# MCU.net
KiCad netlist of a schematic drawn in Altium Designer
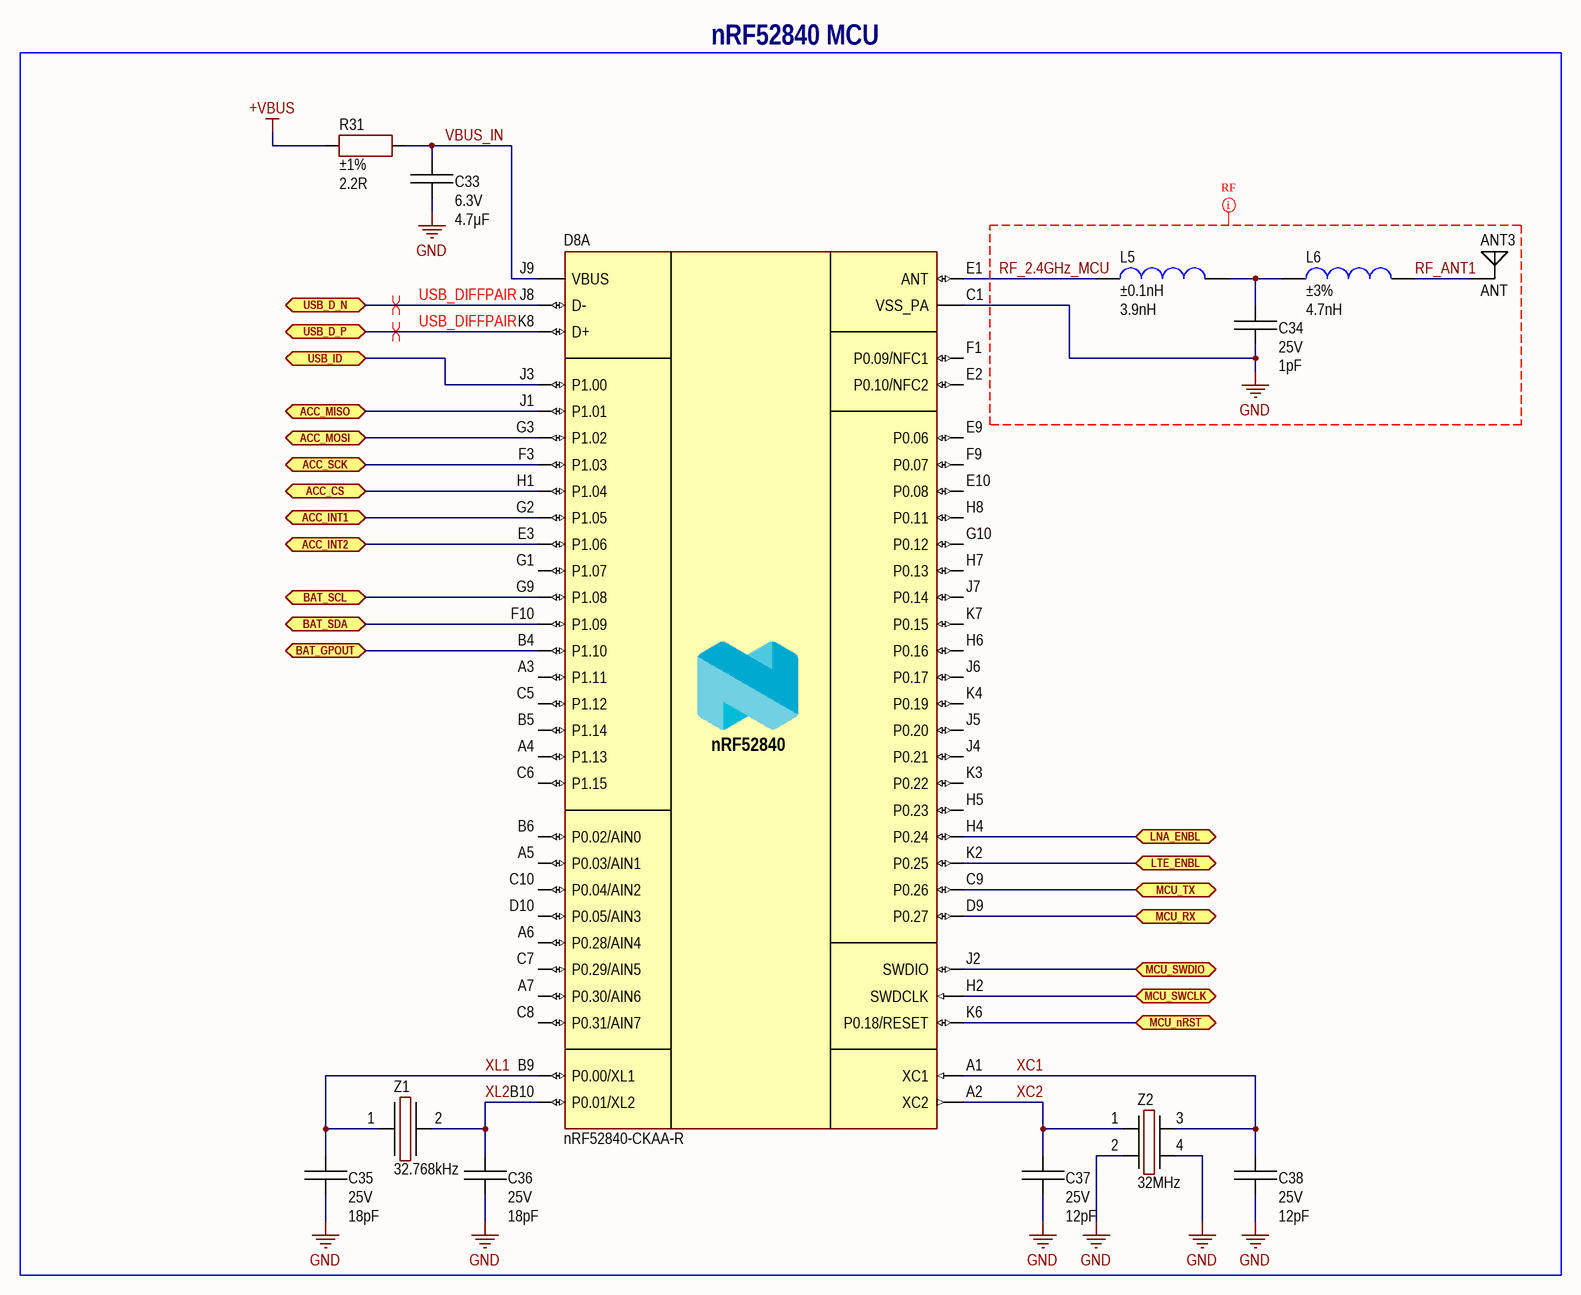
[diagram p0: MCU.SchDoc]

(export (version "E")
  (design (tool "Eeschema 10.0.6"))
  (components
    (comp (ref "ANT3")
      (value "~")
      (footprint "ANT: ANT2012LL00R2400A")
      (description "2.45GHz Bluetooth, ISM, Wi-Fi, Zigbee Chip RF Antenna 2.4GHz ~ 2.5GHz 3.77dBi Solder Surface Mount")
      (fields
        (field (name "MANUFACTURER") "Yageo")
        (field (name "VALUEMANUFACTURERPARTNUMBER") "Ceramic antenna, 2x1.25mm")
        (field (name "COMMENTTEXT") "ANT")
      )
      (libsource (lib "MyLib") (part "ANT2012LL00R2400A"))
    )
    (comp (ref "C33")
      (value "4.7μF")
      (footprint "CAP: 0603_NO_SILK")
      (description "4.7 µF ±20% 6.3V Ceramic Capacitor X7R 0603 (1608 Metric)")
      (fields
        (field (name "MANUFACTURER") "Yageo")
        (field (name "PARTNUMBER") "CC0603MRX7R5BB475")
        (field (name "VOLTAGE") "6.3V")
      )
      (libsource (lib "capacitor") (part "Ceramic_0603"))
    )
    (comp (ref "C34")
      (value "1pF")
      (footprint "CAP: 0201")
      (description "1 pF ±0.05pF 25V Ceramic Capacitor C0G, NP0 0201 (0603 Metric)")
      (fields
        (field (name "MANUFACTURER") "Murata Electronics")
        (field (name "PARTNUMBER") "GJM0335C1E1R0WB01D")
        (field (name "VOLTAGE") "25V")
      )
      (libsource (lib "capacitor") (part "Ceramic_0201"))
    )
    (comp (ref "C35")
      (value "18pF")
      (footprint "CAP: 0201")
      (description "18 pF ±5% 25V Ceramic Capacitor C0G, NP0 0201 (0603 Metric)")
      (fields
        (field (name "MANUFACTURER") "Yageo")
        (field (name "PARTNUMBER") "CC0201JRNPO8BN180")
        (field (name "VOLTAGE") "25V")
      )
      (libsource (lib "capacitor") (part "Ceramic_0201"))
    )
    (comp (ref "C36")
      (value "18pF")
      (footprint "CAP: 0201")
      (description "18 pF ±5% 25V Ceramic Capacitor C0G, NP0 0201 (0603 Metric)")
      (fields
        (field (name "MANUFACTURER") "Yageo")
        (field (name "PARTNUMBER") "CC0201JRNPO8BN180")
        (field (name "VOLTAGE") "25V")
      )
      (libsource (lib "capacitor") (part "Ceramic_0201"))
    )
    (comp (ref "C37")
      (value "12pF")
      (footprint "CAP: 0201")
      (description "12 pF ±5% 25V Ceramic Capacitor C0G, NP0 0201 (0603 Metric)")
      (fields
        (field (name "MANUFACTURER") "Yageo")
        (field (name "PARTNUMBER") "CC0201JRNPO8BN120")
        (field (name "VOLTAGE") "25V")
      )
      (libsource (lib "capacitor") (part "Ceramic_0201"))
    )
    (comp (ref "C38")
      (value "12pF")
      (footprint "CAP: 0201")
      (description "12 pF ±5% 25V Ceramic Capacitor C0G, NP0 0201 (0603 Metric)")
      (fields
        (field (name "MANUFACTURER") "Yageo")
        (field (name "PARTNUMBER") "CC0201JRNPO8BN120")
        (field (name "VOLTAGE") "25V")
      )
      (libsource (lib "capacitor") (part "Ceramic_0201"))
    )
    (comp (ref "D8")
      (value "~")
      (footprint "MCU: nRF52840_WLCP93")
      (description "MCU")
      (fields
        (field (name "MANUFACTURER") "Nordic Semiconductor")
        (field (name "VALUEMANUFACTURERPARTNUMBER") "IC microcontroller, 32bit, Cortex-M4, 64 MHz, 1 MB, 256 kB, , , 93-WLCSP")
        (field (name "PARTNUMBER") "nRF52840-CKAA-R")
      )
      (libsource (lib "MyLib") (part "nRF52840"))
    )
    (comp (ref "L5")
      (value "3.9nH")
      (footprint "IND: 0201")
      (description "3.9 nH Unshielded Thick Film Inductor 400 mA 300mOhm Max 0201 (0603 Metric)")
      (fields
        (field (name "MANUFACTURER") "Murata Electronics")
        (field (name "PARTNUMBER") "LQP03TN3N9B02D")
        (field (name "TOLERANCE") "±0.1nH")
      )
      (libsource (lib "inductor") (part "Inductor_0201"))
    )
    (comp (ref "L6")
      (value "4.7nH")
      (footprint "IND: 0201")
      (description "4.7 nH Unshielded Thick Film Inductor 350 mA 400mOhm Max 0201 (0603 Metric)")
      (fields
        (field (name "MANUFACTURER") "Murata Electronics")
        (field (name "PARTNUMBER") "LQP03TN4N7H02D")
        (field (name "TOLERANCE") "±3%")
      )
      (libsource (lib "inductor") (part "Inductor_0201"))
    )
    (comp (ref "R31")
      (value "2.2R")
      (footprint "RES: 0402")
      (fields
        (field (name "MANUFACTURER") "Yageo")
        (field (name "PARTNUMBER") "RC0402FR-072R2L")
        (field (name "VALUEMANUFACTURERPARTNUMBER") "Resistor film, 2.2R, ±1%, 0402, 0.063W, -55...+125°C")
        (field (name "TOLERANCE") "±1%")
      )
      (libsource (lib "resistor") (part "Resistor_0402"))
    )
    (comp (ref "Z1")
      (value "~")
      (footprint "OSC: 2012")
      (description "Crystal")
      (fields
        (field (name "MANUFACTURER") "Abracon")
        (field (name "PARTNUMBER") "ABS06-32.768KHZ-1-T")
        (field (name "FREQUENCY") "32.768kHz")
      )
      (libsource (lib "MyLib") (part "Crystal_2012"))
    )
    (comp (ref "Z2")
      (value "~")
      (footprint "OSC: 2016")
      (description "32 MHz ±10ppm Crystal 8pF 60 Ohms 4-SMD, No Lead")
      (fields
        (field (name "MANUFACTURER") "EPSON")
        (field (name "PARTNUMBER") "FA-128 32.0000MF10Z-AJ3")
        (field (name "FREQUENCY") "32MHz")
      )
      (libsource (lib "oscilator") (part "Crystal_2016"))
    )
  )
  (nets
    (net (code "1") (name "+VBUS") (class "Default")
      (node (ref "R31") (pin "1") (pinfunction "1_1") (pintype "passive"))
    )
    (net (code "2") (name "/ACC_CS") (class "Default")
      (node (ref "D8") (pin "H1") (pinfunction "P1.04_H1") (pintype "bidirectional"))
    )
    (net (code "3") (name "/ACC_INT1") (class "Default")
      (node (ref "D8") (pin "G2") (pinfunction "P1.05_G2") (pintype "bidirectional"))
    )
    (net (code "4") (name "/ACC_INT2") (class "Default")
      (node (ref "D8") (pin "E3") (pinfunction "P1.06_E3") (pintype "bidirectional"))
    )
    (net (code "5") (name "/ACC_MISO") (class "Default")
      (node (ref "D8") (pin "J1") (pinfunction "P1.01_J1") (pintype "bidirectional"))
    )
    (net (code "6") (name "/ACC_MOSI") (class "Default")
      (node (ref "D8") (pin "G3") (pinfunction "P1.02_G3") (pintype "bidirectional"))
    )
    (net (code "7") (name "/ACC_SCK") (class "Default")
      (node (ref "D8") (pin "F3") (pinfunction "P1.03_F3") (pintype "bidirectional"))
    )
    (net (code "8") (name "/BAT_GPOUT") (class "Default")
      (node (ref "D8") (pin "B4") (pinfunction "P1.10_B4") (pintype "bidirectional"))
    )
    (net (code "9") (name "/BAT_SCL") (class "Default")
      (node (ref "D8") (pin "G9") (pinfunction "P1.08_G9") (pintype "bidirectional"))
    )
    (net (code "10") (name "/BAT_SDA") (class "Default")
      (node (ref "D8") (pin "F10") (pinfunction "P1.09_F10") (pintype "bidirectional"))
    )
    (net (code "11") (name "/LNA_ENBL") (class "Default")
      (node (ref "D8") (pin "H4") (pinfunction "P0.24_H4") (pintype "bidirectional"))
    )
    (net (code "12") (name "/LTE_ENBL") (class "Default")
      (node (ref "D8") (pin "K2") (pinfunction "P0.25_K2") (pintype "bidirectional"))
    )
    (net (code "13") (name "/MCU_RX") (class "Default")
      (node (ref "D8") (pin "D9") (pinfunction "P0.27_D9") (pintype "bidirectional"))
    )
    (net (code "14") (name "/MCU_SWCLK") (class "Default")
      (node (ref "D8") (pin "H2") (pinfunction "SWDCLK_H2") (pintype "input"))
    )
    (net (code "15") (name "/MCU_SWDIO") (class "Default")
      (node (ref "D8") (pin "J2") (pinfunction "SWDIO_J2") (pintype "bidirectional"))
    )
    (net (code "16") (name "/MCU_TX") (class "Default")
      (node (ref "D8") (pin "C9") (pinfunction "P0.26_C9") (pintype "bidirectional"))
    )
    (net (code "17") (name "/MCU_nRST") (class "Default")
      (node (ref "D8") (pin "K6") (pinfunction "P0.18/RESET_K6") (pintype "bidirectional"))
    )
    (net (code "18") (name "/RF_2.4GHz_MCU") (class "Default")
      (node (ref "D8") (pin "E1") (pinfunction "ANT_E1") (pintype "bidirectional"))
      (node (ref "L5") (pin "2") (pinfunction "2_2") (pintype "passive"))
    )
    (net (code "19") (name "/RF_ANT1") (class "Default")
      (node (ref "ANT3") (pin "1") (pinfunction "1_1") (pintype "passive"))
      (node (ref "L6") (pin "1") (pinfunction "1_1") (pintype "passive"))
    )
    (net (code "20") (name "/USB_D_N") (class "Default")
      (node (ref "D8") (pin "J8") (pinfunction "D-_J8") (pintype "bidirectional"))
    )
    (net (code "21") (name "/USB_D_P") (class "Default")
      (node (ref "D8") (pin "K8") (pinfunction "D+_K8") (pintype "bidirectional"))
    )
    (net (code "22") (name "/USB_ID") (class "Default")
      (node (ref "D8") (pin "J3") (pinfunction "P1.00_J3") (pintype "bidirectional"))
    )
    (net (code "23") (name "/VBUS_IN") (class "Default")
      (node (ref "C33") (pin "2") (pinfunction "2_2") (pintype "passive"))
      (node (ref "D8") (pin "J9") (pinfunction "VBUS_J9") (pintype "power_in"))
      (node (ref "R31") (pin "2") (pinfunction "2_2") (pintype "passive"))
    )
    (net (code "24") (name "/XC1") (class "Default")
      (node (ref "C38") (pin "2") (pinfunction "2_2") (pintype "passive"))
      (node (ref "D8") (pin "A1") (pinfunction "XC1_A1") (pintype "input"))
      (node (ref "Z2") (pin "3") (pinfunction "3_3") (pintype "passive"))
    )
    (net (code "25") (name "/XC2") (class "Default")
      (node (ref "C37") (pin "2") (pinfunction "2_2") (pintype "passive"))
      (node (ref "D8") (pin "A2") (pinfunction "XC2_A2") (pintype "output"))
      (node (ref "Z2") (pin "1") (pinfunction "1_1") (pintype "passive"))
    )
    (net (code "26") (name "/XL1") (class "Default")
      (node (ref "C35") (pin "2") (pinfunction "2_2") (pintype "passive"))
      (node (ref "D8") (pin "B9") (pinfunction "P0.00/XL1_B9") (pintype "bidirectional"))
      (node (ref "Z1") (pin "1") (pinfunction "1_1") (pintype "passive"))
    )
    (net (code "27") (name "/XL2") (class "Default")
      (node (ref "C36") (pin "2") (pinfunction "2_2") (pintype "passive"))
      (node (ref "D8") (pin "B10") (pinfunction "P0.01/XL2_B10") (pintype "bidirectional"))
      (node (ref "Z1") (pin "2") (pinfunction "2_2") (pintype "passive"))
    )
    (net (code "28") (name "GND") (class "Default")
      (node (ref "C33") (pin "1") (pinfunction "1_1") (pintype "passive"))
      (node (ref "C34") (pin "1") (pinfunction "1_1") (pintype "passive"))
      (node (ref "C35") (pin "1") (pinfunction "1_1") (pintype "passive"))
      (node (ref "C36") (pin "1") (pinfunction "1_1") (pintype "passive"))
      (node (ref "C37") (pin "1") (pinfunction "1_1") (pintype "passive"))
      (node (ref "C38") (pin "1") (pinfunction "1_1") (pintype "passive"))
      (node (ref "D8") (pin "C1") (pinfunction "VSS_PA_C1") (pintype "power_in"))
      (node (ref "Z2") (pin "2") (pinfunction "2_2") (pintype "passive"))
      (node (ref "Z2") (pin "4") (pinfunction "4_4") (pintype "passive"))
    )
    (net (code "29") (name "Net-(C34-Pad2)") (class "Default")
      (node (ref "C34") (pin "2") (pinfunction "2_2") (pintype "passive"))
      (node (ref "L5") (pin "1") (pinfunction "1_1") (pintype "passive"))
      (node (ref "L6") (pin "2") (pinfunction "2_2") (pintype "passive"))
    )
    (net (code "30") (name "unconnected-(D8A-P0.02{slash}AIN0-PadB6)") (class "Default")
      (node (ref "D8") (pin "B6") (pinfunction "P0.02/AIN0_B6") (pintype "bidirectional"))
    )
    (net (code "31") (name "unconnected-(D8A-P0.03{slash}AIN1-PadA5)") (class "Default")
      (node (ref "D8") (pin "A5") (pinfunction "P0.03/AIN1_A5") (pintype "bidirectional"))
    )
    (net (code "32") (name "unconnected-(D8A-P0.04{slash}AIN2-PadC10)") (class "Default")
      (node (ref "D8") (pin "C10") (pinfunction "P0.04/AIN2_C10") (pintype "bidirectional"))
    )
    (net (code "33") (name "unconnected-(D8A-P0.05{slash}AIN3-PadD10)") (class "Default")
      (node (ref "D8") (pin "D10") (pinfunction "P0.05/AIN3_D10") (pintype "bidirectional"))
    )
    (net (code "34") (name "unconnected-(D8A-P0.06-PadE9)") (class "Default")
      (node (ref "D8") (pin "E9") (pinfunction "P0.06_E9") (pintype "bidirectional"))
    )
    (net (code "35") (name "unconnected-(D8A-P0.07-PadF9)") (class "Default")
      (node (ref "D8") (pin "F9") (pinfunction "P0.07_F9") (pintype "bidirectional"))
    )
    (net (code "36") (name "unconnected-(D8A-P0.08-PadE10)") (class "Default")
      (node (ref "D8") (pin "E10") (pinfunction "P0.08_E10") (pintype "bidirectional"))
    )
    (net (code "37") (name "unconnected-(D8A-P0.09{slash}NFC1-PadF1)") (class "Default")
      (node (ref "D8") (pin "F1") (pinfunction "P0.09/NFC1_F1") (pintype "bidirectional"))
    )
    (net (code "38") (name "unconnected-(D8A-P0.10{slash}NFC2-PadE2)") (class "Default")
      (node (ref "D8") (pin "E2") (pinfunction "P0.10/NFC2_E2") (pintype "bidirectional"))
    )
    (net (code "39") (name "unconnected-(D8A-P0.11-PadH8)") (class "Default")
      (node (ref "D8") (pin "H8") (pinfunction "P0.11_H8") (pintype "bidirectional"))
    )
    (net (code "40") (name "unconnected-(D8A-P0.12-PadG10)") (class "Default")
      (node (ref "D8") (pin "G10") (pinfunction "P0.12_G10") (pintype "bidirectional"))
    )
    (net (code "41") (name "unconnected-(D8A-P0.13-PadH7)") (class "Default")
      (node (ref "D8") (pin "H7") (pinfunction "P0.13_H7") (pintype "bidirectional"))
    )
    (net (code "42") (name "unconnected-(D8A-P0.14-PadJ7)") (class "Default")
      (node (ref "D8") (pin "J7") (pinfunction "P0.14_J7") (pintype "bidirectional"))
    )
    (net (code "43") (name "unconnected-(D8A-P0.15-PadK7)") (class "Default")
      (node (ref "D8") (pin "K7") (pinfunction "P0.15_K7") (pintype "bidirectional"))
    )
    (net (code "44") (name "unconnected-(D8A-P0.16-PadH6)") (class "Default")
      (node (ref "D8") (pin "H6") (pinfunction "P0.16_H6") (pintype "bidirectional"))
    )
    (net (code "45") (name "unconnected-(D8A-P0.17-PadJ6)") (class "Default")
      (node (ref "D8") (pin "J6") (pinfunction "P0.17_J6") (pintype "bidirectional"))
    )
    (net (code "46") (name "unconnected-(D8A-P0.19-PadK4)") (class "Default")
      (node (ref "D8") (pin "K4") (pinfunction "P0.19_K4") (pintype "bidirectional"))
    )
    (net (code "47") (name "unconnected-(D8A-P0.20-PadJ5)") (class "Default")
      (node (ref "D8") (pin "J5") (pinfunction "P0.20_J5") (pintype "bidirectional"))
    )
    (net (code "48") (name "unconnected-(D8A-P0.21-PadJ4)") (class "Default")
      (node (ref "D8") (pin "J4") (pinfunction "P0.21_J4") (pintype "bidirectional"))
    )
    (net (code "49") (name "unconnected-(D8A-P0.22-PadK3)") (class "Default")
      (node (ref "D8") (pin "K3") (pinfunction "P0.22_K3") (pintype "bidirectional"))
    )
    (net (code "50") (name "unconnected-(D8A-P0.23-PadH5)") (class "Default")
      (node (ref "D8") (pin "H5") (pinfunction "P0.23_H5") (pintype "bidirectional"))
    )
    (net (code "51") (name "unconnected-(D8A-P0.28{slash}AIN4-PadA6)") (class "Default")
      (node (ref "D8") (pin "A6") (pinfunction "P0.28/AIN4_A6") (pintype "bidirectional"))
    )
    (net (code "52") (name "unconnected-(D8A-P0.29{slash}AIN5-PadC7)") (class "Default")
      (node (ref "D8") (pin "C7") (pinfunction "P0.29/AIN5_C7") (pintype "bidirectional"))
    )
    (net (code "53") (name "unconnected-(D8A-P0.30{slash}AIN6-PadA7)") (class "Default")
      (node (ref "D8") (pin "A7") (pinfunction "P0.30/AIN6_A7") (pintype "bidirectional"))
    )
    (net (code "54") (name "unconnected-(D8A-P0.31{slash}AIN7-PadC8)") (class "Default")
      (node (ref "D8") (pin "C8") (pinfunction "P0.31/AIN7_C8") (pintype "bidirectional"))
    )
    (net (code "55") (name "unconnected-(D8A-P1.07-PadG1)") (class "Default")
      (node (ref "D8") (pin "G1") (pinfunction "P1.07_G1") (pintype "bidirectional"))
    )
    (net (code "56") (name "unconnected-(D8A-P1.11-PadA3)") (class "Default")
      (node (ref "D8") (pin "A3") (pinfunction "P1.11_A3") (pintype "bidirectional"))
    )
    (net (code "57") (name "unconnected-(D8A-P1.12-PadC5)") (class "Default")
      (node (ref "D8") (pin "C5") (pinfunction "P1.12_C5") (pintype "bidirectional"))
    )
    (net (code "58") (name "unconnected-(D8A-P1.13-PadA4)") (class "Default")
      (node (ref "D8") (pin "A4") (pinfunction "P1.13_A4") (pintype "bidirectional"))
    )
    (net (code "59") (name "unconnected-(D8A-P1.14-PadB5)") (class "Default")
      (node (ref "D8") (pin "B5") (pinfunction "P1.14_B5") (pintype "bidirectional"))
    )
    (net (code "60") (name "unconnected-(D8A-P1.15-PadC6)") (class "Default")
      (node (ref "D8") (pin "C6") (pinfunction "P1.15_C6") (pintype "bidirectional"))
    )
  )
)
